# Breathalyzer.net
KiCad netlist of a schematic drawn in Altium Designer
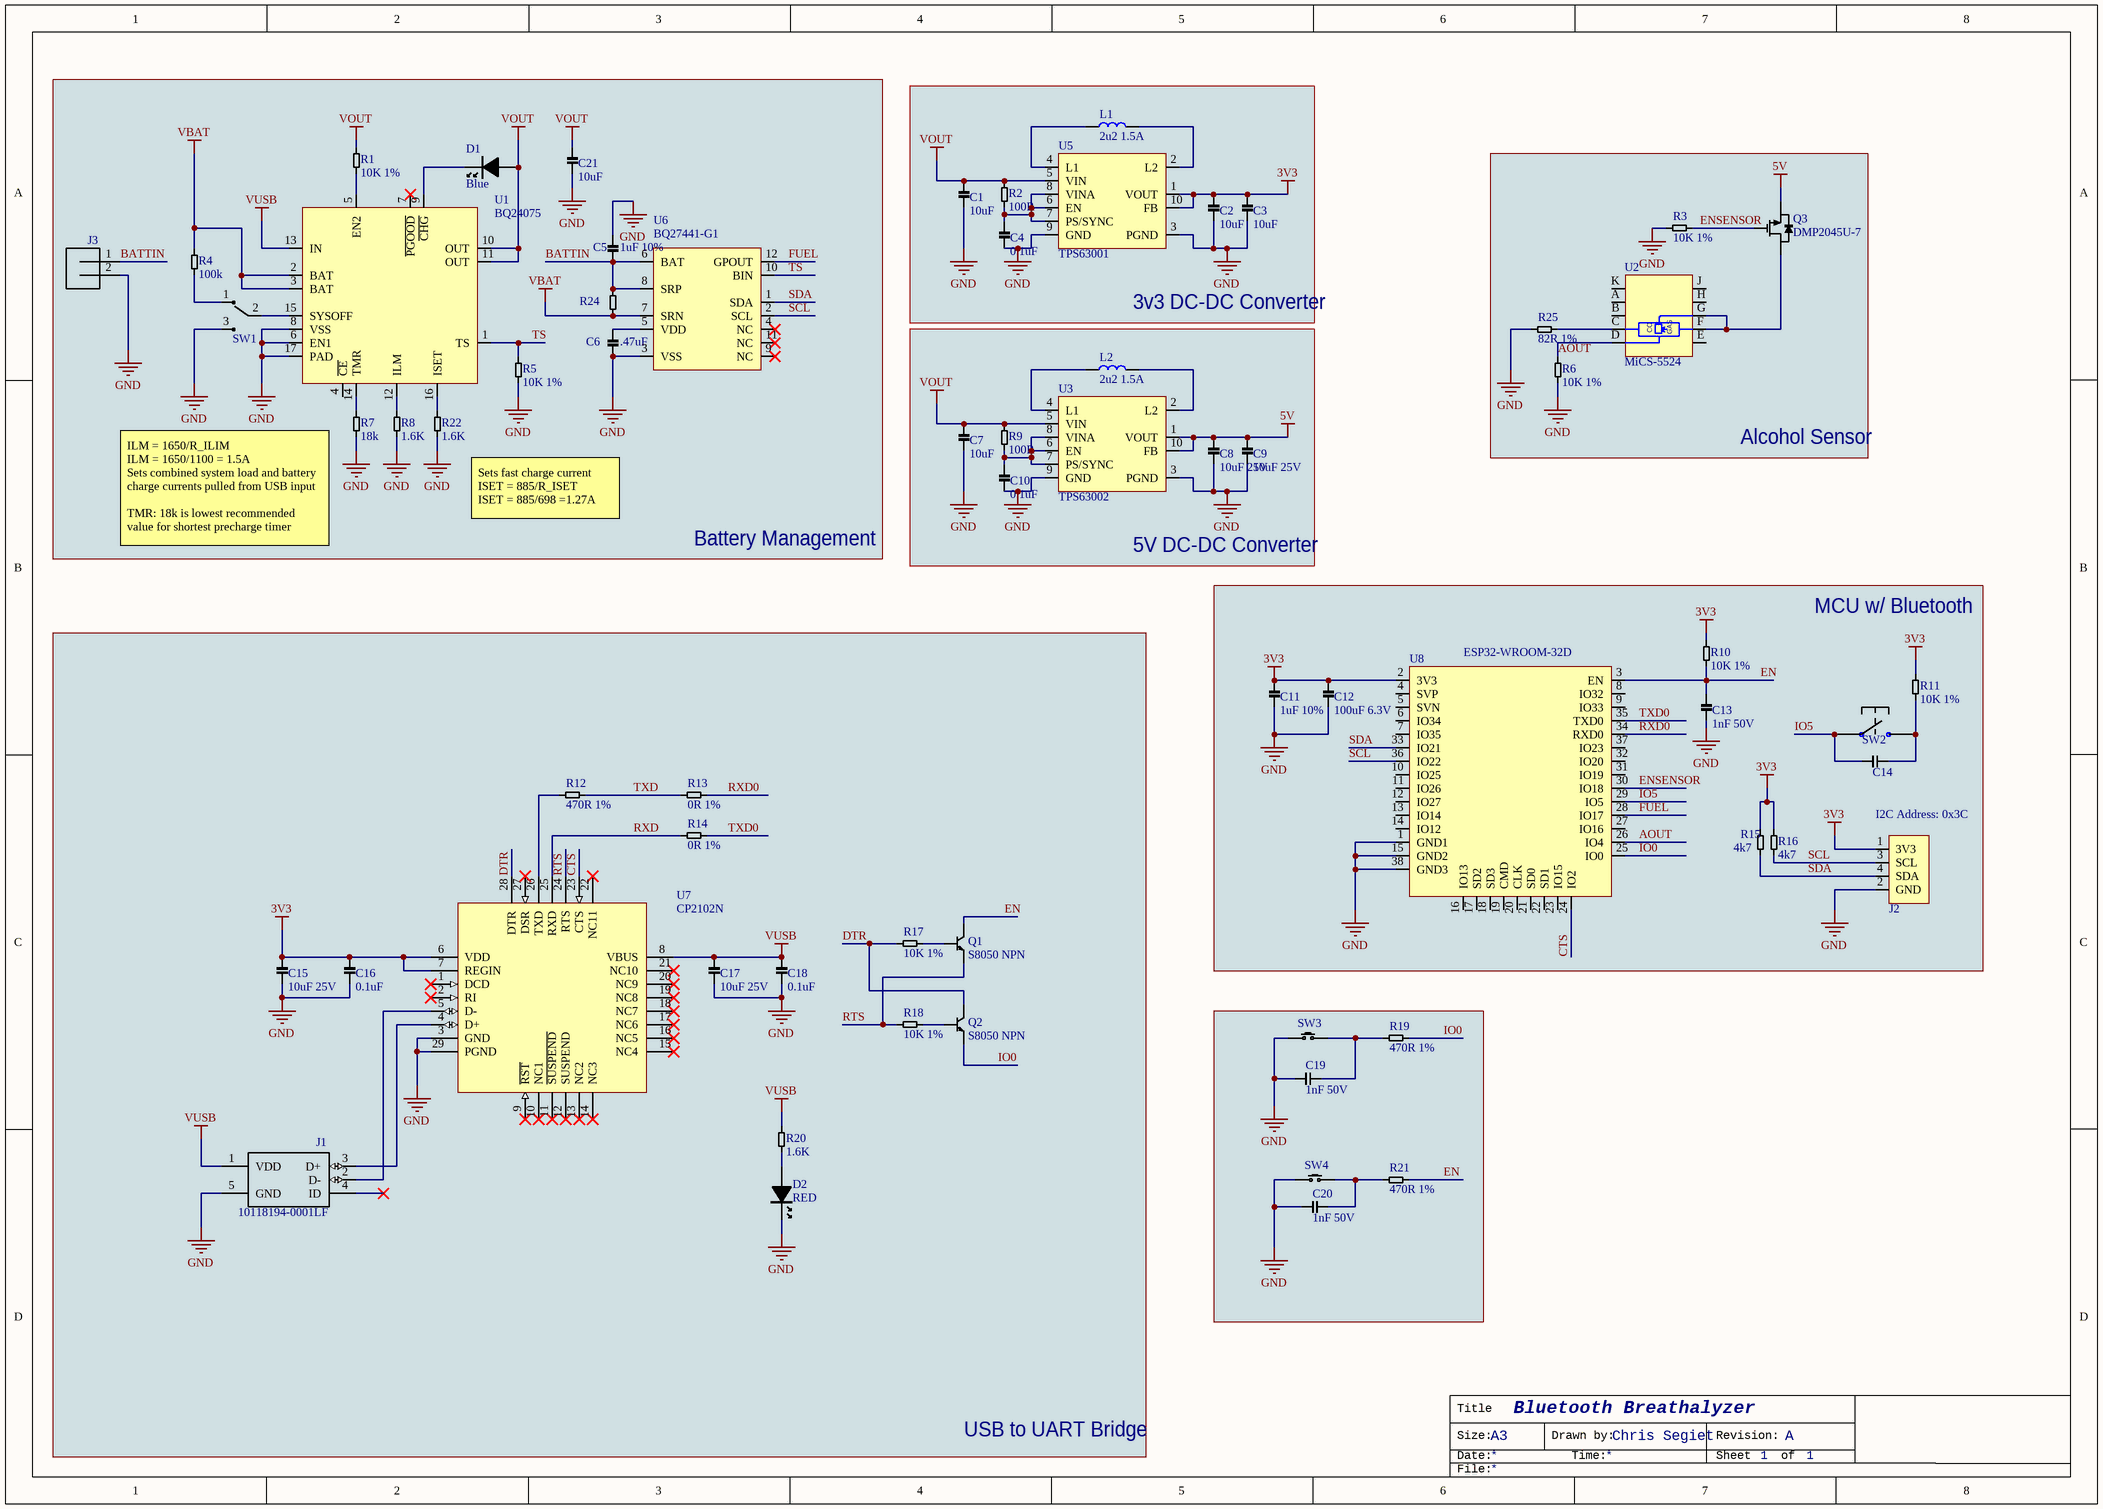
[diagram p0: Breathalyzer.SchDoc]

(export (version "E")
  (design (tool "Eeschema 10.0.6"))
  (components
    (comp (ref "C1")
      (value "10uF")
      (footprint "0805MLCC")
      (description "CAP CER 10UF 6.3V X7R 0805")
      (fields
        (field (name "MANUFACTURER") "Kyocera AVX")
        (field (name "MANUFACTURER PART NUMBER") "08056C106KAT2A")
      )
      (libsource (lib "Breathalyzer") (part "08056C106KAT2A"))
    )
    (comp (ref "C2")
      (value "10uF")
      (footprint "0805MLCC")
      (description "CAP CER 10UF 6.3V X7R 0805")
      (fields
        (field (name "MANUFACTURER") "Kyocera AVX")
        (field (name "MANUFACTURER PART NUMBER") "08056C106KAT2A")
      )
      (libsource (lib "") (part "08056C106KAT2A_1"))
    )
    (comp (ref "C3")
      (value "10uF")
      (footprint "0805MLCC")
      (description "CAP CER 10UF 6.3V X7R 0805")
      (fields
        (field (name "MANUFACTURER") "Kyocera AVX")
        (field (name "MANUFACTURER PART NUMBER") "08056C106KAT2A")
      )
      (libsource (lib "") (part "08056C106KAT2A_1"))
    )
    (comp (ref "C4")
      (value "0.1uF")
      (footprint "0603MLCC")
      (description "CAP CER 0.1UF 25V X7R 0603")
      (fields
        (field (name "MANUFACTURER") "Murata")
        (field (name "MANUFACTURER PART NUMBER") "GRM188R71E104KA01D")
      )
      (libsource (lib "Breathalyzer") (part "GRM188R71E104KA01D"))
    )
    (comp (ref "C5")
      (value "1uF 10%")
      (footprint "0603MLCC")
      (description "Multilayer Ceramic Capacitors MLCC - SMD/SMT 0603 1uF 10volts X5R 10%")
      (fields
        (field (name "MANUFACTURER") "Murata")
        (field (name "MANUFACTURER PART NUMBER") "GRM188R61A105KA61J")
      )
      (libsource (lib "Breathalyzer") (part "GRM188R61A105KA61J"))
    )
    (comp (ref "C6")
      (value ".47uF")
      (footprint "0805MLCC")
      (description "CAP CER 0.47UF 25V X7R 0805")
      (fields
        (field (name "MANUFACTURER") "Yageo")
        (field (name "MANUFACTURER PART NUMBER") "CC0805KKX7R8BB474")
      )
      (libsource (lib "Breathalyzer") (part "CC0805KKX7R8BB474"))
    )
    (comp (ref "C7")
      (value "10uF")
      (footprint "0805MLCC")
      (description "CAP CER 10UF 6.3V X7R 0805")
      (fields
        (field (name "MANUFACTURER") "Kyocera AVX")
        (field (name "MANUFACTURER PART NUMBER") "08056C106KAT2A")
      )
      (libsource (lib "Breathalyzer") (part "08056C106KAT2A"))
    )
    (comp (ref "C8")
      (value "10uF 25V")
      (footprint "1206MLCC")
      (description "CAP CER 10UF 25V X5R 1206")
      (fields
        (field (name "MANUFACTURER") "Taiyo Yuden")
        (field (name "MANUFACTURER PART NUMBER") "TMK316BJ106ML-T")
      )
      (libsource (lib "Breathalyzer") (part "TMK316BJ106ML-T"))
    )
    (comp (ref "C9")
      (value "10uF 25V")
      (footprint "1206MLCC")
      (description "CAP CER 10UF 25V X5R 1206")
      (fields
        (field (name "MANUFACTURER") "Taiyo Yuden")
        (field (name "MANUFACTURER PART NUMBER") "TMK316BJ106ML-T")
      )
      (libsource (lib "Breathalyzer") (part "TMK316BJ106ML-T"))
    )
    (comp (ref "C10")
      (value "0.1uF")
      (footprint "0603MLCC")
      (description "CAP CER 0.1UF 25V X7R 0603")
      (fields
        (field (name "MANUFACTURER") "Murata")
        (field (name "MANUFACTURER PART NUMBER") "GRM188R71E104KA01D")
      )
      (libsource (lib "Breathalyzer") (part "GRM188R71E104KA01D"))
    )
    (comp (ref "C11")
      (value "1uF 10%")
      (footprint "0603MLCC")
      (description "Multilayer Ceramic Capacitors MLCC - SMD/SMT 0603 1uF 10volts X5R 10%")
      (fields
        (field (name "MANUFACTURER") "Murata")
        (field (name "MANUFACTURER PART NUMBER") "GRM188R61A105KA61J")
      )
      (libsource (lib "Breathalyzer") (part "GRM188R61A105KA61J"))
    )
    (comp (ref "C12")
      (value "100uF 6.3V")
      (footprint "1206MLCC")
      (description "Multilayer Ceramic Capacitors MLCC - SMD/SMT 1206 100uF 6.3volt X5R +/-20%")
      (fields
        (field (name "MANUFACTURER") "Murata")
        (field (name "MANUFACTURER PART NUMBER") "GRM31CR60J107ME39K")
      )
      (libsource (lib "Breathalyzer") (part "GRM31CR60J107ME39K"))
    )
    (comp (ref "C13")
      (value "1nF 50V")
      (footprint "0603MLCC")
      (description "CAP CER 1000PF 50V 0603")
      (fields
        (field (name "MANUFACTURER") "Taiyo Yuden")
        (field (name "MANUFACTURER PART NUMBER") "UMK107SD102KA-T")
      )
      (libsource (lib "Breathalyzer") (part "UMK107SD102KA-T"))
    )
    (comp (ref "C14")
      (value "1nF 50V")
      (footprint "0603MLCC")
      (description "CAP CER 1000PF 50V 0603")
      (fields
        (field (name "MANUFACTURER") "Taiyo Yuden")
        (field (name "MANUFACTURER PART NUMBER") "UMK107SD102KA-T")
      )
      (libsource (lib "") (part "UMK107SD102KA-T_2"))
    )
    (comp (ref "C15")
      (value "10uF 25V")
      (footprint "1206MLCC")
      (description "CAP CER 10UF 25V X5R 1206")
      (fields
        (field (name "MANUFACTURER") "Taiyo Yuden")
        (field (name "MANUFACTURER PART NUMBER") "TMK316BJ106ML-T")
      )
      (libsource (lib "Breathalyzer") (part "TMK316BJ106ML-T"))
    )
    (comp (ref "C16")
      (value "0.1uF")
      (footprint "0603MLCC")
      (description "CAP CER 0.1UF 25V X7R 0603")
      (fields
        (field (name "MANUFACTURER") "Murata")
        (field (name "MANUFACTURER PART NUMBER") "GRM188R71E104KA01D")
      )
      (libsource (lib "Breathalyzer") (part "GRM188R71E104KA01D"))
    )
    (comp (ref "C17")
      (value "10uF 25V")
      (footprint "1206MLCC")
      (description "CAP CER 10UF 25V X5R 1206")
      (fields
        (field (name "MANUFACTURER") "Taiyo Yuden")
        (field (name "MANUFACTURER PART NUMBER") "TMK316BJ106ML-T")
      )
      (libsource (lib "Breathalyzer") (part "TMK316BJ106ML-T"))
    )
    (comp (ref "C18")
      (value "0.1uF")
      (footprint "0603MLCC")
      (description "CAP CER 0.1UF 25V X7R 0603")
      (fields
        (field (name "MANUFACTURER") "Murata")
        (field (name "MANUFACTURER PART NUMBER") "GRM188R71E104KA01D")
      )
      (libsource (lib "Breathalyzer") (part "GRM188R71E104KA01D"))
    )
    (comp (ref "C19")
      (value "1nF 50V")
      (footprint "0603MLCC")
      (description "CAP CER 1000PF 50V 0603")
      (fields
        (field (name "MANUFACTURER") "Taiyo Yuden")
        (field (name "MANUFACTURER PART NUMBER") "UMK107SD102KA-T")
      )
      (libsource (lib "") (part "UMK107SD102KA-T_1"))
    )
    (comp (ref "C20")
      (value "1nF 50V")
      (footprint "0603MLCC")
      (description "CAP CER 1000PF 50V 0603")
      (fields
        (field (name "MANUFACTURER") "Taiyo Yuden")
        (field (name "MANUFACTURER PART NUMBER") "UMK107SD102KA-T")
      )
      (libsource (lib "") (part "UMK107SD102KA-T_1"))
    )
    (comp (ref "C21")
      (value "10uF")
      (footprint "0805MLCC")
      (description "CAP CER 10UF 6.3V X7R 0805")
      (fields
        (field (name "MANUFACTURER") "Kyocera AVX")
        (field (name "MANUFACTURER PART NUMBER") "08056C106KAT2A")
      )
      (libsource (lib "Breathalyzer") (part "08056C106KAT2A"))
    )
    (comp (ref "D1")
      (value "Blue")
      (footprint "LTST-C193TBKT-5A")
      (description "Standard LEDs - SMD Blue 470nm 28mcd 5mA")
      (fields
        (field (name "MANUFACTURER") "Vishay Lite-On")
        (field (name "MANUFACTURER PART NUMBER") "LTST-C193TBKT-5A")
      )
      (libsource (lib "Breathalyzer") (part "LTST-C193TBKT-5A"))
    )
    (comp (ref "D2")
      (value "RED")
      (footprint "LEDC2012X75N_APT2012SRCPRV(Primary)")
      (description "LED 2X1.2MM 640NM RD WTR CLR SMD")
      (fields
        (field (name "MANUFACTURER") "Kingbright")
        (field (name "MANUFACTURER PART NUMBER") "APT2012SRCPRV")
      )
      (libsource (lib "Breathalyzer") (part "APT2012SRCPRV"))
    )
    (comp (ref "J1")
      (value "10118194-0001LF")
      (footprint "FRAMATOME_10118194-0001LF")
      (description "Conn Micro USB Type B RCP 5 POS 0.65mm Solder RA SMD 5 Terminal 1 Port T/R")
      (fields (field (name "MF") "Amphenol FCI"))
      (libsource (lib "Breathalyzer") (part "10118194-0001LF"))
    )
    (comp (ref "J2")
      (value "Header for I2C Testing")
      (footprint "1x4 Header 2.54mm pitch")
      (description "1x4 Header for I2C Testing")
      (libsource (lib "Breathalyzer") (part "I2C Testing"))
    )
    (comp (ref "J3")
      (value "S2B-PH-SM4-TB")
      (footprint "JST_S2B-PH-SM4-TB")
      (description "Socket; wire-board; male; PIN: 2; 2mm; SMT; PH; 100V; 2A; -25Ã·85Â°C")
      (fields (field (name "MF") "JST"))
      (libsource (lib "Breathalyzer") (part "S2B-PH-SM4-TB"))
    )
    (comp (ref "L1")
      (value "2u2 1.5A")
      (footprint "VLF4012AT-2R2M1R5")
      (description "FIXED IND 2.2UH 1.5A 87 MOHM SMD")
      (fields
        (field (name "MANUFACTURER") "TDK")
        (field (name "MANUFACTURER PART NUMBER") "VLF4012AT-2R2M1R5")
      )
      (libsource (lib "Breathalyzer") (part "VLF4012AT-2R2M1R5"))
    )
    (comp (ref "L2")
      (value "2u2 1.5A")
      (footprint "VLF4012AT-2R2M1R5")
      (description "FIXED IND 2.2UH 1.5A 87 MOHM SMD")
      (fields
        (field (name "MANUFACTURER") "TDK")
        (field (name "MANUFACTURER PART NUMBER") "VLF4012AT-2R2M1R5")
      )
      (libsource (lib "Breathalyzer") (part "VLF4012AT-2R2M1R5"))
    )
    (comp (ref "Q1")
      (value "S8050 NPN")
      (footprint "SOT23-NPN")
      (description "TRANS NPN 25V 1.5A SOT-23")
      (fields (field (name "MANUFACTURER") "MCC") (field (name "MANUFACTURER PART NUMBER") "MMSS8050-L-TP"))
      (libsource (lib "Breathalyzer") (part "MMSS8050-L-TP"))
    )
    (comp (ref "Q2")
      (value "S8050 NPN")
      (footprint "SOT23-NPN")
      (description "TRANS NPN 25V 1.5A SOT-23")
      (fields (field (name "MANUFACTURER") "MCC") (field (name "MANUFACTURER PART NUMBER") "MMSS8050-L-TP"))
      (libsource (lib "Breathalyzer") (part "MMSS8050-L-TP"))
    )
    (comp (ref "Q3")
      (value "DMP2045U-7")
      (footprint "SOT91P240X110-3N")
      (description "P-Channel MOSFET 045R at VGS=-4.5V ID = -4.3A")
      (fields (field (name "MANUFACTURER") "Diodes"))
      (libsource (lib "Breathalyzer") (part "DMP2045U-7"))
    )
    (comp (ref "R1")
      (value "10K 1%")
      (footprint "0805RES")
      (description "RES SMD 10K OHM 1% 1/8W 0805")
      (fields
        (field (name "MANUFACTURER") "Yageo")
        (field (name "MANUFACTURER PART NUMBER") "RC0805FR-0710KL")
      )
      (libsource (lib "Breathalyzer") (part "RC0805FR-0710KL"))
    )
    (comp (ref "R2")
      (value "100R")
      (footprint "0805RES")
      (description "RES, THICK FILM, 100R, 5%, 0.125W, 0805")
      (fields
        (field (name "MANUFACTURER") "Yageo")
        (field (name "MANUFACTURER PART NUMBER") "RC0805JR-07100RL")
      )
      (libsource (lib "Breathalyzer") (part "RC0805JR-07100RL"))
    )
    (comp (ref "R3")
      (value "10K 1%")
      (footprint "0805RES")
      (description "RES SMD 10K OHM 1% 1/8W 0805")
      (fields
        (field (name "MANUFACTURER") "Yageo")
        (field (name "MANUFACTURER PART NUMBER") "RC0805FR-0710KL")
      )
      (libsource (lib "") (part "RC0805FR-0710KL_2"))
    )
    (comp (ref "R4")
      (value "100k")
      (footprint "0603RES")
      (description "YAGEO         RC0603FR-07100KL             RES, THICK FILM, 100K, 1%, 0.1W, 0603")
      (fields
        (field (name "MANUFACTURER") "Yageo")
        (field (name "MANUFACTURER PART NUMBER") "RC0603FR-07100KL")
      )
      (libsource (lib "Breathalyzer") (part "RC0603FR-07100KL"))
    )
    (comp (ref "R5")
      (value "10K 1%")
      (footprint "0805RES")
      (description "RES SMD 10K OHM 1% 1/8W 0805")
      (fields
        (field (name "MANUFACTURER") "Yageo")
        (field (name "MANUFACTURER PART NUMBER") "RC0805FR-0710KL")
      )
      (libsource (lib "Breathalyzer") (part "RC0805FR-0710KL"))
    )
    (comp (ref "R6")
      (value "10K 1%")
      (footprint "0805RES")
      (description "RES SMD 10K OHM 1% 1/8W 0805")
      (fields
        (field (name "MANUFACTURER") "Yageo")
        (field (name "MANUFACTURER PART NUMBER") "RC0805FR-0710KL")
      )
      (libsource (lib "Breathalyzer") (part "RC0805FR-0710KL"))
    )
    (comp (ref "R7")
      (value "18k")
      (footprint "0805RES")
      (description "RES SMD 18K OHM 1% 1/8W 0805")
      (fields
        (field (name "MANUFACTURER") "Vishay")
        (field (name "MANUFACTURER PART NUMBER") "CRCW080518K0FKEA")
      )
      (libsource (lib "Breathalyzer") (part "CRCW080518K0FKEA"))
    )
    (comp (ref "R8")
      (value "1.6K")
      (footprint "0805RES")
      (description "RES SMD 1.6K OHM 1% 1/8W 0805")
      (fields
        (field (name "MANUFACTURER") "Vishay")
        (field (name "MANUFACTURER PART NUMBER") "CRCW08051K60FKEA")
      )
      (libsource (lib "Breathalyzer") (part "CRCW08051K60FKEA"))
    )
    (comp (ref "R9")
      (value "100R")
      (footprint "0805RES")
      (description "RES, THICK FILM, 100R, 5%, 0.125W, 0805")
      (fields
        (field (name "MANUFACTURER") "Yageo")
        (field (name "MANUFACTURER PART NUMBER") "RC0805JR-07100RL")
      )
      (libsource (lib "Breathalyzer") (part "RC0805JR-07100RL"))
    )
    (comp (ref "R10")
      (value "10K 1%")
      (footprint "0805RES")
      (description "RES SMD 10K OHM 1% 1/8W 0805")
      (fields
        (field (name "MANUFACTURER") "Yageo")
        (field (name "MANUFACTURER PART NUMBER") "RC0805FR-0710KL")
      )
      (libsource (lib "Breathalyzer") (part "RC0805FR-0710KL"))
    )
    (comp (ref "R11")
      (value "10K 1%")
      (footprint "0805RES")
      (description "RES SMD 10K OHM 1% 1/8W 0805")
      (fields
        (field (name "MANUFACTURER") "Yageo")
        (field (name "MANUFACTURER PART NUMBER") "RC0805FR-0710KL")
      )
      (libsource (lib "Breathalyzer") (part "RC0805FR-0710KL"))
    )
    (comp (ref "R12")
      (value "470R 1%")
      (footprint "0805RES")
      (description "RES SMD 470 OHM 1% 1/8W 0805")
      (fields
        (field (name "MANUFACTURER") "Yageo")
        (field (name "MANUFACTURER PART NUMBER") "RC0805FR-07470RL")
      )
      (libsource (lib "Breathalyzer") (part "RC0805FR-07470RL"))
    )
    (comp (ref "R13")
      (value "0R 1%")
      (footprint "0603RES")
      (description "Thick Film Resistors - SMD 0.0ohm 1%")
      (fields
        (field (name "MANUFACTURER") "Yageo")
        (field (name "MANUFACTURER PART NUMBER") "RC0603FR-070RL")
      )
      (libsource (lib "Breathalyzer") (part "RC0603FR-070RL"))
    )
    (comp (ref "R14")
      (value "0R 1%")
      (footprint "0603RES")
      (description "Thick Film Resistors - SMD 0.0ohm 1%")
      (fields
        (field (name "MANUFACTURER") "Yageo")
        (field (name "MANUFACTURER PART NUMBER") "RC0603FR-070RL")
      )
      (libsource (lib "Breathalyzer") (part "RC0603FR-070RL"))
    )
    (comp (ref "R15")
      (value "4k7")
      (footprint "0805RES")
      (description "YAGEO         RC0805JR-074K7L             RES, THICK FILM, 4K7, 5%, 0.125W, 0805")
      (fields
        (field (name "MANUFACTURER") "Yageo")
        (field (name "MANUFACTURER PART NUMBER") "RC0805JR-074K7L")
      )
      (libsource (lib "") (part "RC0805JR-074K7L_1"))
    )
    (comp (ref "R16")
      (value "4k7")
      (footprint "0805RES")
      (description "YAGEO         RC0805JR-074K7L             RES, THICK FILM, 4K7, 5%, 0.125W, 0805")
      (fields
        (field (name "MANUFACTURER") "Yageo")
        (field (name "MANUFACTURER PART NUMBER") "RC0805JR-074K7L")
      )
      (libsource (lib "Breathalyzer") (part "RC0805JR-074K7L"))
    )
    (comp (ref "R17")
      (value "10K 1%")
      (footprint "0805RES")
      (description "RES SMD 10K OHM 1% 1/8W 0805")
      (fields
        (field (name "MANUFACTURER") "Yageo")
        (field (name "MANUFACTURER PART NUMBER") "RC0805FR-0710KL")
      )
      (libsource (lib "") (part "RC0805FR-0710KL_1"))
    )
    (comp (ref "R18")
      (value "10K 1%")
      (footprint "0805RES")
      (description "RES SMD 10K OHM 1% 1/8W 0805")
      (fields
        (field (name "MANUFACTURER") "Yageo")
        (field (name "MANUFACTURER PART NUMBER") "RC0805FR-0710KL")
      )
      (libsource (lib "") (part "RC0805FR-0710KL_1"))
    )
    (comp (ref "R19")
      (value "470R 1%")
      (footprint "0805RES")
      (description "RES SMD 470 OHM 1% 1/8W 0805")
      (fields
        (field (name "MANUFACTURER") "Yageo")
        (field (name "MANUFACTURER PART NUMBER") "RC0805FR-07470RL")
      )
      (libsource (lib "Breathalyzer") (part "RC0805FR-07470RL"))
    )
    (comp (ref "R20")
      (value "1.6K")
      (footprint "0805RES")
      (description "RES SMD 1.6K OHM 1% 1/8W 0805")
      (fields
        (field (name "MANUFACTURER") "Vishay")
        (field (name "MANUFACTURER PART NUMBER") "CRCW08051K60FKEA")
      )
      (libsource (lib "Breathalyzer") (part "CRCW08051K60FKEA"))
    )
    (comp (ref "R21")
      (value "470R 1%")
      (footprint "0805RES")
      (description "RES SMD 470 OHM 1% 1/8W 0805")
      (fields
        (field (name "MANUFACTURER") "Yageo")
        (field (name "MANUFACTURER PART NUMBER") "RC0805FR-07470RL")
      )
      (libsource (lib "Breathalyzer") (part "RC0805FR-07470RL"))
    )
    (comp (ref "R22")
      (value "1.6K")
      (footprint "0805RES")
      (description "RES SMD 1.6K OHM 1% 1/8W 0805")
      (fields
        (field (name "MANUFACTURER") "Vishay")
        (field (name "MANUFACTURER PART NUMBER") "CRCW08051K60FKEA")
      )
      (libsource (lib "Breathalyzer") (part "CRCW08051K60FKEA"))
    )
    (comp (ref "R24")
      (value "0.01R 1% 1W")
      (footprint "1206RES")
      (description "Current Sense Resistor, 0.01 ohm, 1206 [3216 Metric], 1 W,  1%, ERJ8B Series")
      (fields
        (field (name "MANUFACTURER") "Panasonic")
        (field (name "MANUFACTURER PART NUMBER") "ERJ-8BWFR010V")
      )
      (libsource (lib "Breathalyzer") (part "ERJ-8BWFR010V"))
    )
    (comp (ref "R25")
      (value "82R 1%")
      (footprint "0805RES")
      (description "RES SMD 82 OHM 1% 1/8W 0805")
      (fields
        (field (name "MANUFACTURER") "Vishay")
        (field (name "MANUFACTURER PART NUMBER") "CRCW080582R0FKEA")
      )
      (libsource (lib "Breathalyzer") (part "CRCW080582R0FKEA"))
    )
    (comp (ref "SW1")
      (value "PCM12SMTR")
      (footprint "SW_PCM12SMTR_PCM12SMTR(Primary)")
      (description "C & K COMPONENTS         PCM12SMTR             Slide Switch, SPDT, On-On, SMD, PCM Series, 300 mA")
      (fields (field (name "MANUFACTURER") "ITT C&K"))
      (libsource (lib "Breathalyzer") (part "PCM12SMTR"))
    )
    (comp (ref "SW2")
      (value "PTS645SM43SMTR")
      (footprint "PTS645SM43SMTR")
      (description "Switch Tact 6mm 100gf h=4.3mm")
      (fields (field (name "MF") "C&K"))
      (libsource (lib "Breathalyzer") (part "PTS645SM43SMTR"))
    )
    (comp (ref "SW3")
      (value "SMD Light Touch Switch")
      (footprint "Tactile Switch")
      (description "Tactile Switch")
      (fields (field (name "MANUFACTURER") "Panasonic") (field (name "MANUFACTURER PART NUMBER") "EVPAWCD4A"))
      (libsource (lib "Breathalyzer") (part "EVPAWCD4A"))
    )
    (comp (ref "SW4")
      (value "SMD Light Touch Switch")
      (footprint "Tactile Switch")
      (description "Tactile Switch")
      (fields (field (name "MANUFACTURER") "Panasonic") (field (name "MANUFACTURER PART NUMBER") "EVPAWCD4A"))
      (libsource (lib "Breathalyzer") (part "EVPAWCD4A"))
    )
    (comp (ref "U1")
      (value "BQ24075")
      (footprint "VQFN 16-pin 0.5mm pitch")
      (description "TEXAS INSTRUMENTS   BQ24075RGTT   IC, BATTERY CHARGER,LI-ION, 1.5A, QFN-16")
      (fields
        (field (name "MANUFACTURER") "Texas Instruments")
        (field (name "MANUFACTURER PART NUMBER") "BQ24075RGTT")
      )
      (libsource (lib "Breathalyzer") (part "BQ24075RGTT"))
    )
    (comp (ref "U2")
      (value "MiCS-5524")
      (footprint "MiCS5524 Ethanol Sensor")
      (description "10-500ppm Ethanol Sensor")
      (fields (field (name "MANUFACTURER") "Amphenol SGX Sensortech"))
      (libsource (lib "Breathalyzer") (part "MiCS-5524"))
    )
    (comp (ref "U3")
      (value "TPS63002")
      (footprint "SON50P300X300X100-11N")
      (description "IC REG BUCK BOOST 5V 1.6A 10SON")
      (fields
        (field (name "MANUFACTURER") "Texas Instruments")
        (field (name "MANUFACTURER PART NUMBER") "TPS63002DRCR")
      )
      (libsource (lib "Breathalyzer") (part "TPS63002DRCR"))
    )
    (comp (ref "U5")
      (value "TPS63001")
      (footprint "SON50P300X300X100-11N")
      (description "Conv DC-DC Single Non-Inv/Inv/Step Up/Step Down 1.8V to 5.5V 10-Pin VSON EP T/R")
      (fields
        (field (name "MANUFACTURER") "Texas Instruments")
        (field (name "MANUFACTURER PART NUMBER") "TPS63001DRCT")
      )
      (libsource (lib "Breathalyzer") (part "TPS63001DRCT"))
    )
    (comp (ref "U6")
      (value "BQ27441-G1")
      (footprint "SON40P400X250X100-13N")
      (description "IC BATT FUEL GAUGE LI-ION 12SON")
      (fields
        (field (name "MANUFACTURER") "Texas Instruments")
        (field (name "MANUFACTURER PART NUMBER") "BQ27441DRZR-G1A")
      )
      (libsource (lib "Breathalyzer") (part "BQ27441DRZR-G1A"))
    )
    (comp (ref "U7")
      (value "CP2102N")
      (footprint "QFN50P500X500X80-29N")
      (fields
        (field (name "MANUFACTURER") "Silicon Labs")
        (field (name "MANUFACTURER PART NUMBER") "CP2102N-A01-GQFN28")
      )
      (libsource (lib "Breathalyzer") (part "CP2102N-A01-GQFN28"))
    )
    (comp (ref "U8")
      (value "ESP32-WROOM-32D")
      (footprint "MODULE_ESP32-WROOM-32D")
      (description "ESP32 Module")
      (fields (field (name "MANUFACTURER") "Espressif Systems"))
      (libsource (lib "Breathalyzer") (part "ESP32-WROOM-32D"))
    )
  )
  (nets
    (net (code "1") (name "/AOUT") (class "Default")
      (node (ref "R6") (pin "2") (pinfunction "2_2") (pintype "passive"))
      (node (ref "U2") (pin "D") (pinfunction "D_D") (pintype "passive"))
      (node (ref "U8") (pin "26") (pinfunction "IO4_26") (pintype "bidirectional"))
    )
    (net (code "2") (name "/BATTIN") (class "Default")
      (node (ref "C5") (pin "1") (pinfunction "1_1") (pintype "passive"))
      (node (ref "J3") (pin "1") (pinfunction "1_1") (pintype "passive"))
      (node (ref "R24") (pin "2") (pinfunction "2_2") (pintype "passive"))
      (node (ref "U6") (pin "6") (pinfunction "BAT_6") (pintype "passive"))
      (node (ref "U6") (pin "8") (pinfunction "SRP_8") (pintype "passive"))
    )
    (net (code "3") (name "/CTS") (class "Default")
      (node (ref "U7") (pin "23") (pinfunction "CTS_23") (pintype "input"))
      (node (ref "U8") (pin "24") (pinfunction "IO2_24") (pintype "bidirectional"))
    )
    (net (code "4") (name "/DTR") (class "Default")
      (node (ref "Q2") (pin "C") (pinfunction "C_C") (pintype "passive"))
      (node (ref "R17") (pin "1") (pinfunction "1_1") (pintype "passive"))
      (node (ref "U7") (pin "28") (pinfunction "DTR_28") (pintype "passive"))
    )
    (net (code "5") (name "/EN") (class "Default")
      (node (ref "C13") (pin "2") (pinfunction "2_2") (pintype "passive"))
      (node (ref "Q1") (pin "C") (pinfunction "C_C") (pintype "passive"))
      (node (ref "R10") (pin "1") (pinfunction "1_1") (pintype "passive"))
      (node (ref "R21") (pin "2") (pinfunction "2_2") (pintype "passive"))
      (node (ref "U8") (pin "3") (pinfunction "EN_3") (pintype "passive"))
    )
    (net (code "6") (name "/ENSENSOR") (class "Default")
      (node (ref "Q3") (pin "G") (pinfunction "G_G") (pintype "passive"))
      (node (ref "R3") (pin "1") (pinfunction "1_1") (pintype "passive"))
      (node (ref "U8") (pin "30") (pinfunction "IO18_30") (pintype "bidirectional"))
    )
    (net (code "7") (name "/FUEL") (class "Default")
      (node (ref "U6") (pin "12") (pinfunction "GPOUT_12") (pintype "passive"))
      (node (ref "U8") (pin "28") (pinfunction "IO17_28") (pintype "bidirectional"))
    )
    (net (code "8") (name "/IO0") (class "Default")
      (node (ref "Q2") (pin "E") (pinfunction "E_E") (pintype "passive"))
      (node (ref "R19") (pin "2") (pinfunction "2_2") (pintype "passive"))
      (node (ref "U8") (pin "25") (pinfunction "IO0_25") (pintype "bidirectional"))
    )
    (net (code "9") (name "/IO5") (class "Default")
      (node (ref "C14") (pin "2") (pinfunction "2_2") (pintype "passive"))
      (node (ref "SW2") (pin "1") (pinfunction "P$1_1") (pintype "passive"))
      (node (ref "SW2") (pin "2") (pinfunction "P$1_2") (pintype "passive"))
      (node (ref "U8") (pin "29") (pinfunction "IO5_29") (pintype "bidirectional"))
    )
    (net (code "10") (name "/RTS") (class "Default")
      (node (ref "Q1") (pin "E") (pinfunction "E_E") (pintype "passive"))
      (node (ref "R18") (pin "1") (pinfunction "1_1") (pintype "passive"))
      (node (ref "U7") (pin "24") (pinfunction "RTS_24") (pintype "passive"))
    )
    (net (code "11") (name "/RXD") (class "Default")
      (node (ref "R14") (pin "1") (pinfunction "1_1") (pintype "passive"))
      (node (ref "U7") (pin "25") (pinfunction "RXD_25") (pintype "passive"))
    )
    (net (code "12") (name "/RXD0") (class "Default")
      (node (ref "R13") (pin "2") (pinfunction "2_2") (pintype "passive"))
      (node (ref "U8") (pin "34") (pinfunction "RXD0_34") (pintype "bidirectional"))
    )
    (net (code "13") (name "/SCL") (class "Default")
      (node (ref "J2") (pin "3") (pinfunction "SCL_3") (pintype "passive"))
      (node (ref "R16") (pin "1") (pinfunction "1_1") (pintype "passive"))
      (node (ref "U6") (pin "2") (pinfunction "SCL_2") (pintype "passive"))
      (node (ref "U8") (pin "36") (pinfunction "IO22_36") (pintype "bidirectional"))
    )
    (net (code "14") (name "/SDA") (class "Default")
      (node (ref "J2") (pin "4") (pinfunction "SDA_4") (pintype "passive"))
      (node (ref "R15") (pin "2") (pinfunction "2_2") (pintype "passive"))
      (node (ref "U6") (pin "1") (pinfunction "SDA_1") (pintype "passive"))
      (node (ref "U8") (pin "33") (pinfunction "IO21_33") (pintype "bidirectional"))
    )
    (net (code "15") (name "/TS") (class "Default")
      (node (ref "R5") (pin "2") (pinfunction "2_2") (pintype "passive"))
      (node (ref "U1") (pin "1") (pinfunction "TS_1") (pintype "passive"))
      (node (ref "U6") (pin "10") (pinfunction "BIN_10") (pintype "passive"))
    )
    (net (code "16") (name "/TXD") (class "Default")
      (node (ref "R12") (pin "2") (pinfunction "2_2") (pintype "passive"))
      (node (ref "R13") (pin "1") (pinfunction "1_1") (pintype "passive"))
    )
    (net (code "17") (name "/TXD0") (class "Default")
      (node (ref "R14") (pin "2") (pinfunction "2_2") (pintype "passive"))
      (node (ref "U8") (pin "35") (pinfunction "TXD0_35") (pintype "bidirectional"))
    )
    (net (code "18") (name "3V3") (class "Default")
      (node (ref "C11") (pin "2") (pinfunction "2_2") (pintype "passive"))
      (node (ref "C12") (pin "2") (pinfunction "2_2") (pintype "passive"))
      (node (ref "C15") (pin "2") (pinfunction "2_2") (pintype "passive"))
      (node (ref "C16") (pin "2") (pinfunction "2_2") (pintype "passive"))
      (node (ref "C2") (pin "2") (pinfunction "2_2") (pintype "passive"))
      (node (ref "C3") (pin "2") (pinfunction "2_2") (pintype "passive"))
      (node (ref "J2") (pin "1") (pinfunction "3V3_1") (pintype "passive"))
      (node (ref "R10") (pin "2") (pinfunction "2_2") (pintype "passive"))
      (node (ref "R11") (pin "2") (pinfunction "2_2") (pintype "passive"))
      (node (ref "R15") (pin "1") (pinfunction "1_1") (pintype "passive"))
      (node (ref "R16") (pin "2") (pinfunction "2_2") (pintype "passive"))
      (node (ref "U5") (pin "1") (pinfunction "VOUT_1") (pintype "passive"))
      (node (ref "U5") (pin "10") (pinfunction "FB_10") (pintype "passive"))
      (node (ref "U7") (pin "6") (pinfunction "VDD_6") (pintype "passive"))
      (node (ref "U7") (pin "7") (pinfunction "REGIN_7") (pintype "passive"))
      (node (ref "U8") (pin "2") (pinfunction "3V3_2") (pintype "passive"))
    )
    (net (code "19") (name "5V") (class "Default")
      (node (ref "C8") (pin "2") (pinfunction "2_2") (pintype "passive"))
      (node (ref "C9") (pin "2") (pinfunction "2_2") (pintype "passive"))
      (node (ref "Q3") (pin "S") (pinfunction "S_S") (pintype "passive"))
      (node (ref "U3") (pin "1") (pinfunction "VOUT_1") (pintype "passive"))
      (node (ref "U3") (pin "10") (pinfunction "FB_10") (pintype "passive"))
    )
    (net (code "20") (name "GND") (class "Default")
      (node (ref "C1") (pin "2") (pinfunction "2_2") (pintype "passive"))
      (node (ref "C10") (pin "1") (pinfunction "1_1") (pintype "passive"))
      (node (ref "C11") (pin "1") (pinfunction "1_1") (pintype "passive"))
      (node (ref "C12") (pin "1") (pinfunction "1_1") (pintype "passive"))
      (node (ref "C13") (pin "1") (pinfunction "1_1") (pintype "passive"))
      (node (ref "C15") (pin "1") (pinfunction "1_1") (pintype "passive"))
      (node (ref "C16") (pin "1") (pinfunction "1_1") (pintype "passive"))
      (node (ref "C17") (pin "1") (pinfunction "1_1") (pintype "passive"))
      (node (ref "C18") (pin "1") (pinfunction "1_1") (pintype "passive"))
      (node (ref "C19") (pin "1") (pinfunction "1_1") (pintype "passive"))
      (node (ref "C2") (pin "1") (pinfunction "1_1") (pintype "passive"))
      (node (ref "C20") (pin "1") (pinfunction "1_1") (pintype "passive"))
      (node (ref "C21") (pin "2") (pinfunction "2_2") (pintype "passive"))
      (node (ref "C3") (pin "1") (pinfunction "1_1") (pintype "passive"))
      (node (ref "C4") (pin "1") (pinfunction "1_1") (pintype "passive"))
      (node (ref "C5") (pin "2") (pinfunction "2_2") (pintype "passive"))
      (node (ref "C6") (pin "1") (pinfunction "1_1") (pintype "passive"))
      (node (ref "C7") (pin "2") (pinfunction "2_2") (pintype "passive"))
      (node (ref "C8") (pin "1") (pinfunction "1_1") (pintype "passive"))
      (node (ref "C9") (pin "1") (pinfunction "1_1") (pintype "passive"))
      (node (ref "D2") (pin "2") (pinfunction "2_2") (pintype "passive"))
      (node (ref "J1") (pin "5") (pinfunction "GND_5") (pintype "power_in"))
      (node (ref "J2") (pin "2") (pinfunction "GND_2") (pintype "passive"))
      (node (ref "J3") (pin "2") (pinfunction "2_2") (pintype "passive"))
      (node (ref "R22") (pin "1") (pinfunction "1_1") (pintype "passive"))
      (node (ref "R25") (pin "1") (pinfunction "1_1") (pintype "passive"))
      (node (ref "R3") (pin "2") (pinfunction "2_2") (pintype "passive"))
      (node (ref "R5") (pin "1") (pinfunction "1_1") (pintype "passive"))
      (node (ref "R6") (pin "1") (pinfunction "1_1") (pintype "passive"))
      (node (ref "R7") (pin "1") (pinfunction "1_1") (pintype "passive"))
      (node (ref "R8") (pin "1") (pinfunction "1_1") (pintype "passive"))
      (node (ref "SW1") (pin "3") (pinfunction "3_3") (pintype "passive"))
      (node (ref "SW3") (pin "1") (pinfunction "1_1") (pintype "passive"))
      (node (ref "SW4") (pin "1") (pinfunction "1_1") (pintype "passive"))
      (node (ref "U1") (pin "17") (pinfunction "PAD_17") (pintype "passive"))
      (node (ref "U1") (pin "6") (pinfunction "EN1_6") (pintype "passive"))
      (node (ref "U1") (pin "8") (pinfunction "VSS_8") (pintype "passive"))
      (node (ref "U3") (pin "3") (pinfunction "PGND_3") (pintype "passive"))
      (node (ref "U3") (pin "9") (pinfunction "GND_9") (pintype "passive"))
      (node (ref "U5") (pin "3") (pinfunction "PGND_3") (pintype "passive"))
      (node (ref "U5") (pin "9") (pinfunction "GND_9") (pintype "passive"))
      (node (ref "U6") (pin "3") (pinfunction "VSS_3") (pintype "passive"))
      (node (ref "U7") (pin "29") (pinfunction "PGND_29") (pintype "passive"))
      (node (ref "U7") (pin "3") (pinfunction "GND_3") (pintype "passive"))
      (node (ref "U8") (pin "1") (pinfunction "GND1_1") (pintype "passive"))
      (node (ref "U8") (pin "15") (pinfunction "GND2_15") (pintype "passive"))
      (node (ref "U8") (pin "38") (pinfunction "GND3_38") (pintype "passive"))
    )
    (net (code "21") (name "Net-(C14-Pad1)") (class "Default")
      (node (ref "C14") (pin "1") (pinfunction "1_1") (pintype "passive"))
      (node (ref "R11") (pin "1") (pinfunction "1_1") (pintype "passive"))
      (node (ref "SW2") (pin "3") (pinfunction "P$2_3") (pintype "passive"))
      (node (ref "SW2") (pin "4") (pinfunction "P$2_4") (pintype "passive"))
    )
    (net (code "22") (name "Net-(C19-Pad2)") (class "Default")
      (node (ref "C19") (pin "2") (pinfunction "2_2") (pintype "passive"))
      (node (ref "R19") (pin "1") (pinfunction "1_1") (pintype "passive"))
      (node (ref "SW3") (pin "2") (pinfunction "2_2") (pintype "passive"))
    )
    (net (code "23") (name "Net-(C20-Pad2)") (class "Default")
      (node (ref "C20") (pin "2") (pinfunction "2_2") (pintype "passive"))
      (node (ref "R21") (pin "1") (pinfunction "1_1") (pintype "passive"))
      (node (ref "SW4") (pin "2") (pinfunction "2_2") (pintype "passive"))
    )
    (net (code "24") (name "Net-(D2-Pad1)") (class "Default")
      (node (ref "D2") (pin "1") (pinfunction "1_1") (pintype "passive"))
      (node (ref "R20") (pin "1") (pinfunction "1_1") (pintype "passive"))
    )
    (net (code "25") (name "Net-(J1-D+)") (class "Default")
      (node (ref "J1") (pin "3") (pinfunction "D+_3") (pintype "bidirectional"))
      (node (ref "U7") (pin "4") (pinfunction "D+_4") (pintype "bidirectional"))
    )
    (net (code "26") (name "Net-(J1-D-)") (class "Default")
      (node (ref "J1") (pin "2") (pinfunction "D-_2") (pintype "bidirectional"))
      (node (ref "U7") (pin "5") (pinfunction "D-_5") (pintype "bidirectional"))
    )
    (net (code "27") (name "Net-(Q1-PadB)") (class "Default")
      (node (ref "Q1") (pin "B") (pinfunction "B_B") (pintype "passive"))
      (node (ref "R17") (pin "2") (pinfunction "2_2") (pintype "passive"))
    )
    (net (code "28") (name "Net-(Q2-PadB)") (class "Default")
      (node (ref "Q2") (pin "B") (pinfunction "B_B") (pintype "passive"))
      (node (ref "R18") (pin "2") (pinfunction "2_2") (pintype "passive"))
    )
    (net (code "29") (name "Net-(Q3-PadD)") (class "Default")
      (node (ref "Q3") (pin "D") (pinfunction "D_D") (pintype "passive"))
      (node (ref "U2") (pin "F") (pinfunction "F_F") (pintype "passive"))
      (node (ref "U2") (pin "G") (pinfunction "G_G") (pintype "passive"))
    )
    (net (code "30") (name "Net-(R4-Pad1)") (class "Default")
      (node (ref "R4") (pin "1") (pinfunction "1_1") (pintype "passive"))
      (node (ref "SW1") (pin "1") (pinfunction "1_1") (pintype "passive"))
    )
    (net (code "31") (name "Net-(R25-Pad2)") (class "Default")
      (node (ref "R25") (pin "2") (pinfunction "2_2") (pintype "passive"))
      (node (ref "U2") (pin "C") (pinfunction "C_C") (pintype "passive"))
    )
    (net (code "32") (name "Net-(U1-EN2)") (class "Default")
      (node (ref "R1") (pin "1") (pinfunction "1_1") (pintype "passive"))
      (node (ref "U1") (pin "5") (pinfunction "EN2_5") (pintype "passive"))
    )
    (net (code "33") (name "Net-(U1-ILM)") (class "Default")
      (node (ref "R8") (pin "2") (pinfunction "2_2") (pintype "passive"))
      (node (ref "U1") (pin "12") (pinfunction "ILM_12") (pintype "passive"))
    )
    (net (code "34") (name "Net-(U1-ISET)") (class "Default")
      (node (ref "R22") (pin "2") (pinfunction "2_2") (pintype "passive"))
      (node (ref "U1") (pin "16") (pinfunction "ISET_16") (pintype "passive"))
    )
    (net (code "35") (name "Net-(U1-SYSOFF)") (class "Default")
      (node (ref "SW1") (pin "2") (pinfunction "2_2") (pintype "passive"))
      (node (ref "U1") (pin "15") (pinfunction "SYSOFF_15") (pintype "passive"))
    )
    (net (code "36") (name "Net-(U1-TMR)") (class "Default")
      (node (ref "R7") (pin "2") (pinfunction "2_2") (pintype "passive"))
      (node (ref "U1") (pin "14") (pinfunction "TMR_14") (pintype "passive"))
    )
    (net (code "37") (name "Net-(U1-~{CHG})") (class "Default")
      (node (ref "D1") (pin "2") (pinfunction "2_2") (pintype "passive"))
      (node (ref "U1") (pin "9") (pinfunction "~{CHG}_9") (pintype "passive"))
    )
    (net (code "38") (name "Net-(U3-EN)") (class "Default")
      (node (ref "C10") (pin "2") (pinfunction "2_2") (pintype "passive"))
      (node (ref "R9") (pin "1") (pinfunction "1_1") (pintype "passive"))
      (node (ref "U3") (pin "6") (pinfunction "EN_6") (pintype "passive"))
      (node (ref "U3") (pin "7") (pinfunction "PS/SYNC_7") (pintype "passive"))
      (node (ref "U3") (pin "8") (pinfunction "VINA_8") (pintype "passive"))
    )
    (net (code "39") (name "Net-(U3-L1)") (class "Default")
      (node (ref "L2") (pin "1") (pinfunction "1_1") (pintype "passive"))
      (node (ref "U3") (pin "4") (pinfunction "L1_4") (pintype "passive"))
    )
    (net (code "40") (name "Net-(U3-L2)") (class "Default")
      (node (ref "L2") (pin "2") (pinfunction "2_2") (pintype "passive"))
      (node (ref "U3") (pin "2") (pinfunction "L2_2") (pintype "passive"))
    )
    (net (code "41") (name "Net-(U5-EN)") (class "Default")
      (node (ref "C4") (pin "2") (pinfunction "2_2") (pintype "passive"))
      (node (ref "R2") (pin "1") (pinfunction "1_1") (pintype "passive"))
      (node (ref "U5") (pin "6") (pinfunction "EN_6") (pintype "passive"))
      (node (ref "U5") (pin "7") (pinfunction "PS/SYNC_7") (pintype "passive"))
      (node (ref "U5") (pin "8") (pinfunction "VINA_8") (pintype "passive"))
    )
    (net (code "42") (name "Net-(U5-L1)") (class "Default")
      (node (ref "L1") (pin "1") (pinfunction "1_1") (pintype "passive"))
      (node (ref "U5") (pin "4") (pinfunction "L1_4") (pintype "passive"))
    )
    (net (code "43") (name "Net-(U5-L2)") (class "Default")
      (node (ref "L1") (pin "2") (pinfunction "2_2") (pintype "passive"))
      (node (ref "U5") (pin "2") (pinfunction "L2_2") (pintype "passive"))
    )
    (net (code "44") (name "Net-(U6-VDD)") (class "Default")
      (node (ref "C6") (pin "2") (pinfunction "2_2") (pintype "passive"))
      (node (ref "U6") (pin "5") (pinfunction "VDD_5") (pintype "passive"))
    )
    (net (code "45") (name "Net-(U7-TXD)") (class "Default")
      (node (ref "R12") (pin "1") (pinfunction "1_1") (pintype "passive"))
      (node (ref "U7") (pin "26") (pinfunction "TXD_26") (pintype "passive"))
    )
    (net (code "46") (name "VBAT") (class "Default")
      (node (ref "R24") (pin "1") (pinfunction "1_1") (pintype "passive"))
      (node (ref "R4") (pin "2") (pinfunction "2_2") (pintype "passive"))
      (node (ref "U1") (pin "2") (pinfunction "BAT_2") (pintype "passive"))
      (node (ref "U1") (pin "3") (pinfunction "BAT_3") (pintype "passive"))
      (node (ref "U6") (pin "7") (pinfunction "SRN_7") (pintype "passive"))
    )
    (net (code "47") (name "VOUT") (class "Default")
      (node (ref "C1") (pin "1") (pinfunction "1_1") (pintype "passive"))
      (node (ref "C21") (pin "1") (pinfunction "1_1") (pintype "passive"))
      (node (ref "C7") (pin "1") (pinfunction "1_1") (pintype "passive"))
      (node (ref "D1") (pin "1") (pinfunction "1_1") (pintype "passive"))
      (node (ref "R1") (pin "2") (pinfunction "2_2") (pintype "passive"))
      (node (ref "R2") (pin "2") (pinfunction "2_2") (pintype "passive"))
      (node (ref "R9") (pin "2") (pinfunction "2_2") (pintype "passive"))
      (node (ref "U1") (pin "10") (pinfunction "OUT_10") (pintype "passive"))
      (node (ref "U1") (pin "11") (pinfunction "OUT_11") (pintype "passive"))
      (node (ref "U3") (pin "5") (pinfunction "VIN_5") (pintype "passive"))
      (node (ref "U5") (pin "5") (pinfunction "VIN_5") (pintype "passive"))
    )
    (net (code "48") (name "VUSB") (class "Default")
      (node (ref "C17") (pin "2") (pinfunction "2_2") (pintype "passive"))
      (node (ref "C18") (pin "2") (pinfunction "2_2") (pintype "passive"))
      (node (ref "J1") (pin "1") (pinfunction "VDD_1") (pintype "power_in"))
      (node (ref "R20") (pin "2") (pinfunction "2_2") (pintype "passive"))
      (node (ref "U1") (pin "13") (pinfunction "IN_13") (pintype "passive"))
      (node (ref "U7") (pin "8") (pinfunction "VBUS_8") (pintype "power_in"))
    )
    (net (code "49") (name "unconnected-(J1-ID-Pad4)") (class "Default")
      (node (ref "J1") (pin "4") (pinfunction "ID_4") (pintype "passive+no_connect"))
    )
    (net (code "50") (name "unconnected-(U1-~{CE}-Pad4)") (class "Default")
      (node (ref "U1") (pin "4") (pinfunction "~{CE}_4") (pintype "passive"))
    )
    (net (code "51") (name "unconnected-(U1-~{PGOOD}-Pad7)") (class "Default")
      (node (ref "U1") (pin "7") (pinfunction "~{PGOOD}_7") (pintype "passive+no_connect"))
    )
    (net (code "52") (name "unconnected-(U2-PadA)") (class "Default")
      (node (ref "U2") (pin "A") (pinfunction "A_A") (pintype "passive"))
    )
    (net (code "53") (name "unconnected-(U2-PadB)") (class "Default")
      (node (ref "U2") (pin "B") (pinfunction "B_B") (pintype "passive"))
    )
    (net (code "54") (name "unconnected-(U2-PadE)") (class "Default")
      (node (ref "U2") (pin "E") (pinfunction "E_E") (pintype "passive"))
    )
    (net (code "55") (name "unconnected-(U2-PadH)") (class "Default")
      (node (ref "U2") (pin "H") (pinfunction "H_H") (pintype "passive"))
    )
    (net (code "56") (name "unconnected-(U2-PadJ)") (class "Default")
      (node (ref "U2") (pin "J") (pinfunction "J_J") (pintype "passive"))
    )
    (net (code "57") (name "unconnected-(U2-PadK)") (class "Default")
      (node (ref "U2") (pin "K") (pinfunction "K_K") (pintype "passive"))
    )
    (net (code "58") (name "unconnected-(U6-NC-Pad4)") (class "Default")
      (node (ref "U6") (pin "4") (pinfunction "NC_4") (pintype "passive+no_connect"))
    )
    (net (code "59") (name "unconnected-(U6-NC-Pad9)") (class "Default")
      (node (ref "U6") (pin "9") (pinfunction "NC_9") (pintype "passive+no_connect"))
    )
    (net (code "60") (name "unconnected-(U6-NC-Pad11)") (class "Default")
      (node (ref "U6") (pin "11") (pinfunction "NC_11") (pintype "passive+no_connect"))
    )
    (net (code "61") (name "unconnected-(U7-DCD-Pad1)") (class "Default")
      (node (ref "U7") (pin "1") (pinfunction "DCD_1") (pintype "input+no_connect"))
    )
    (net (code "62") (name "unconnected-(U7-DSR-Pad27)") (class "Default")
      (node (ref "U7") (pin "27") (pinfunction "DSR_27") (pintype "input+no_connect"))
    )
    (net (code "63") (name "unconnected-(U7-NC1-Pad10)") (class "Default")
      (node (ref "U7") (pin "10") (pinfunction "NC1_10") (pintype "passive+no_connect"))
    )
    (net (code "64") (name "unconnected-(U7-NC2-Pad13)") (class "Default")
      (node (ref "U7") (pin "13") (pinfunction "NC2_13") (pintype "passive+no_connect"))
    )
    (net (code "65") (name "unconnected-(U7-NC3-Pad14)") (class "Default")
      (node (ref "U7") (pin "14") (pinfunction "NC3_14") (pintype "passive+no_connect"))
    )
    (net (code "66") (name "unconnected-(U7-NC4-Pad15)") (class "Default")
      (node (ref "U7") (pin "15") (pinfunction "NC4_15") (pintype "passive+no_connect"))
    )
    (net (code "67") (name "unconnected-(U7-NC5-Pad16)") (class "Default")
      (node (ref "U7") (pin "16") (pinfunction "NC5_16") (pintype "passive+no_connect"))
    )
    (net (code "68") (name "unconnected-(U7-NC6-Pad17)") (class "Default")
      (node (ref "U7") (pin "17") (pinfunction "NC6_17") (pintype "passive+no_connect"))
    )
    (net (code "69") (name "unconnected-(U7-NC7-Pad18)") (class "Default")
      (node (ref "U7") (pin "18") (pinfunction "NC7_18") (pintype "passive+no_connect"))
    )
    (net (code "70") (name "unconnected-(U7-NC8-Pad19)") (class "Default")
      (node (ref "U7") (pin "19") (pinfunction "NC8_19") (pintype "passive+no_connect"))
    )
    (net (code "71") (name "unconnected-(U7-NC9-Pad20)") (class "Default")
      (node (ref "U7") (pin "20") (pinfunction "NC9_20") (pintype "passive+no_connect"))
    )
    (net (code "72") (name "unconnected-(U7-NC10-Pad21)") (class "Default")
      (node (ref "U7") (pin "21") (pinfunction "NC10_21") (pintype "passive+no_connect"))
    )
    (net (code "73") (name "unconnected-(U7-NC11-Pad22)") (class "Default")
      (node (ref "U7") (pin "22") (pinfunction "NC11_22") (pintype "passive+no_connect"))
    )
    (net (code "74") (name "unconnected-(U7-RI-Pad2)") (class "Default")
      (node (ref "U7") (pin "2") (pinfunction "RI_2") (pintype "input+no_connect"))
    )
    (net (code "75") (name "unconnected-(U7-SUSPEND-Pad12)") (class "Default")
      (node (ref "U7") (pin "12") (pinfunction "SUSPEND_12") (pintype "passive+no_connect"))
    )
    (net (code "76") (name "unconnected-(U7-~{RST}-Pad9)") (class "Default")
      (node (ref "U7") (pin "9") (pinfunction "~{RST}_9") (pintype "input+no_connect"))
    )
    (net (code "77") (name "unconnected-(U7-~{SUSPEND}-Pad11)") (class "Default")
      (node (ref "U7") (pin "11") (pinfunction "~{SUSPEND}_11") (pintype "passive+no_connect"))
    )
    (net (code "78") (name "unconnected-(U8-CLK-Pad20)") (class "Default")
      (node (ref "U8") (pin "20") (pinfunction "CLK_20") (pintype "passive"))
    )
    (net (code "79") (name "unconnected-(U8-CMD-Pad19)") (class "Default")
      (node (ref "U8") (pin "19") (pinfunction "CMD_19") (pintype "passive"))
    )
    (net (code "80") (name "unconnected-(U8-IO12-Pad14)") (class "Default")
      (node (ref "U8") (pin "14") (pinfunction "IO12_14") (pintype "bidirectional"))
    )
    (net (code "81") (name "unconnected-(U8-IO13-Pad16)") (class "Default")
      (node (ref "U8") (pin "16") (pinfunction "IO13_16") (pintype "bidirectional"))
    )
    (net (code "82") (name "unconnected-(U8-IO14-Pad13)") (class "Default")
      (node (ref "U8") (pin "13") (pinfunction "IO14_13") (pintype "bidirectional"))
    )
    (net (code "83") (name "unconnected-(U8-IO15-Pad23)") (class "Default")
      (node (ref "U8") (pin "23") (pinfunction "IO15_23") (pintype "bidirectional"))
    )
    (net (code "84") (name "unconnected-(U8-IO16-Pad27)") (class "Default")
      (node (ref "U8") (pin "27") (pinfunction "IO16_27") (pintype "bidirectional"))
    )
    (net (code "85") (name "unconnected-(U8-IO19-Pad31)") (class "Default")
      (node (ref "U8") (pin "31") (pinfunction "IO19_31") (pintype "bidirectional"))
    )
    (net (code "86") (name "unconnected-(U8-IO20-Pad32)") (class "Default")
      (node (ref "U8") (pin "32") (pinfunction "IO20_32") (pintype "bidirectional"))
    )
    (net (code "87") (name "unconnected-(U8-IO23-Pad37)") (class "Default")
      (node (ref "U8") (pin "37") (pinfunction "IO23_37") (pintype "bidirectional"))
    )
    (net (code "88") (name "unconnected-(U8-IO25-Pad10)") (class "Default")
      (node (ref "U8") (pin "10") (pinfunction "IO25_10") (pintype "bidirectional"))
    )
    (net (code "89") (name "unconnected-(U8-IO26-Pad11)") (class "Default")
      (node (ref "U8") (pin "11") (pinfunction "IO26_11") (pintype "bidirectional"))
    )
    (net (code "90") (name "unconnected-(U8-IO27-Pad12)") (class "Default")
      (node (ref "U8") (pin "12") (pinfunction "IO27_12") (pintype "bidirectional"))
    )
    (net (code "91") (name "unconnected-(U8-IO32-Pad8)") (class "Default")
      (node (ref "U8") (pin "8") (pinfunction "IO32_8") (pintype "bidirectional"))
    )
    (net (code "92") (name "unconnected-(U8-IO33-Pad9)") (class "Default")
      (node (ref "U8") (pin "9") (pinfunction "IO33_9") (pintype "bidirectional"))
    )
    (net (code "93") (name "unconnected-(U8-IO34-Pad6)") (class "Default")
      (node (ref "U8") (pin "6") (pinfunction "IO34_6") (pintype "bidirectional"))
    )
    (net (code "94") (name "unconnected-(U8-IO35-Pad7)") (class "Default")
      (node (ref "U8") (pin "7") (pinfunction "IO35_7") (pintype "bidirectional"))
    )
    (net (code "95") (name "unconnected-(U8-SD0-Pad21)") (class "Default")
      (node (ref "U8") (pin "21") (pinfunction "SD0_21") (pintype "passive"))
    )
    (net (code "96") (name "unconnected-(U8-SD1-Pad22)") (class "Default")
      (node (ref "U8") (pin "22") (pinfunction "SD1_22") (pintype "passive"))
    )
    (net (code "97") (name "unconnected-(U8-SD2-Pad17)") (class "Default")
      (node (ref "U8") (pin "17") (pinfunction "SD2_17") (pintype "passive"))
    )
    (net (code "98") (name "unconnected-(U8-SD3-Pad18)") (class "Default")
      (node (ref "U8") (pin "18") (pinfunction "SD3_18") (pintype "passive"))
    )
    (net (code "99") (name "unconnected-(U8-SVN-Pad5)") (class "Default")
      (node (ref "U8") (pin "5") (pinfunction "SVN_5") (pintype "passive"))
    )
    (net (code "100") (name "unconnected-(U8-SVP-Pad4)") (class "Default")
      (node (ref "U8") (pin "4") (pinfunction "SVP_4") (pintype "passive"))
    )
  )
)
